# WikiHub-Mini.net
KiCad netlist of a schematic drawn in Altium Designer
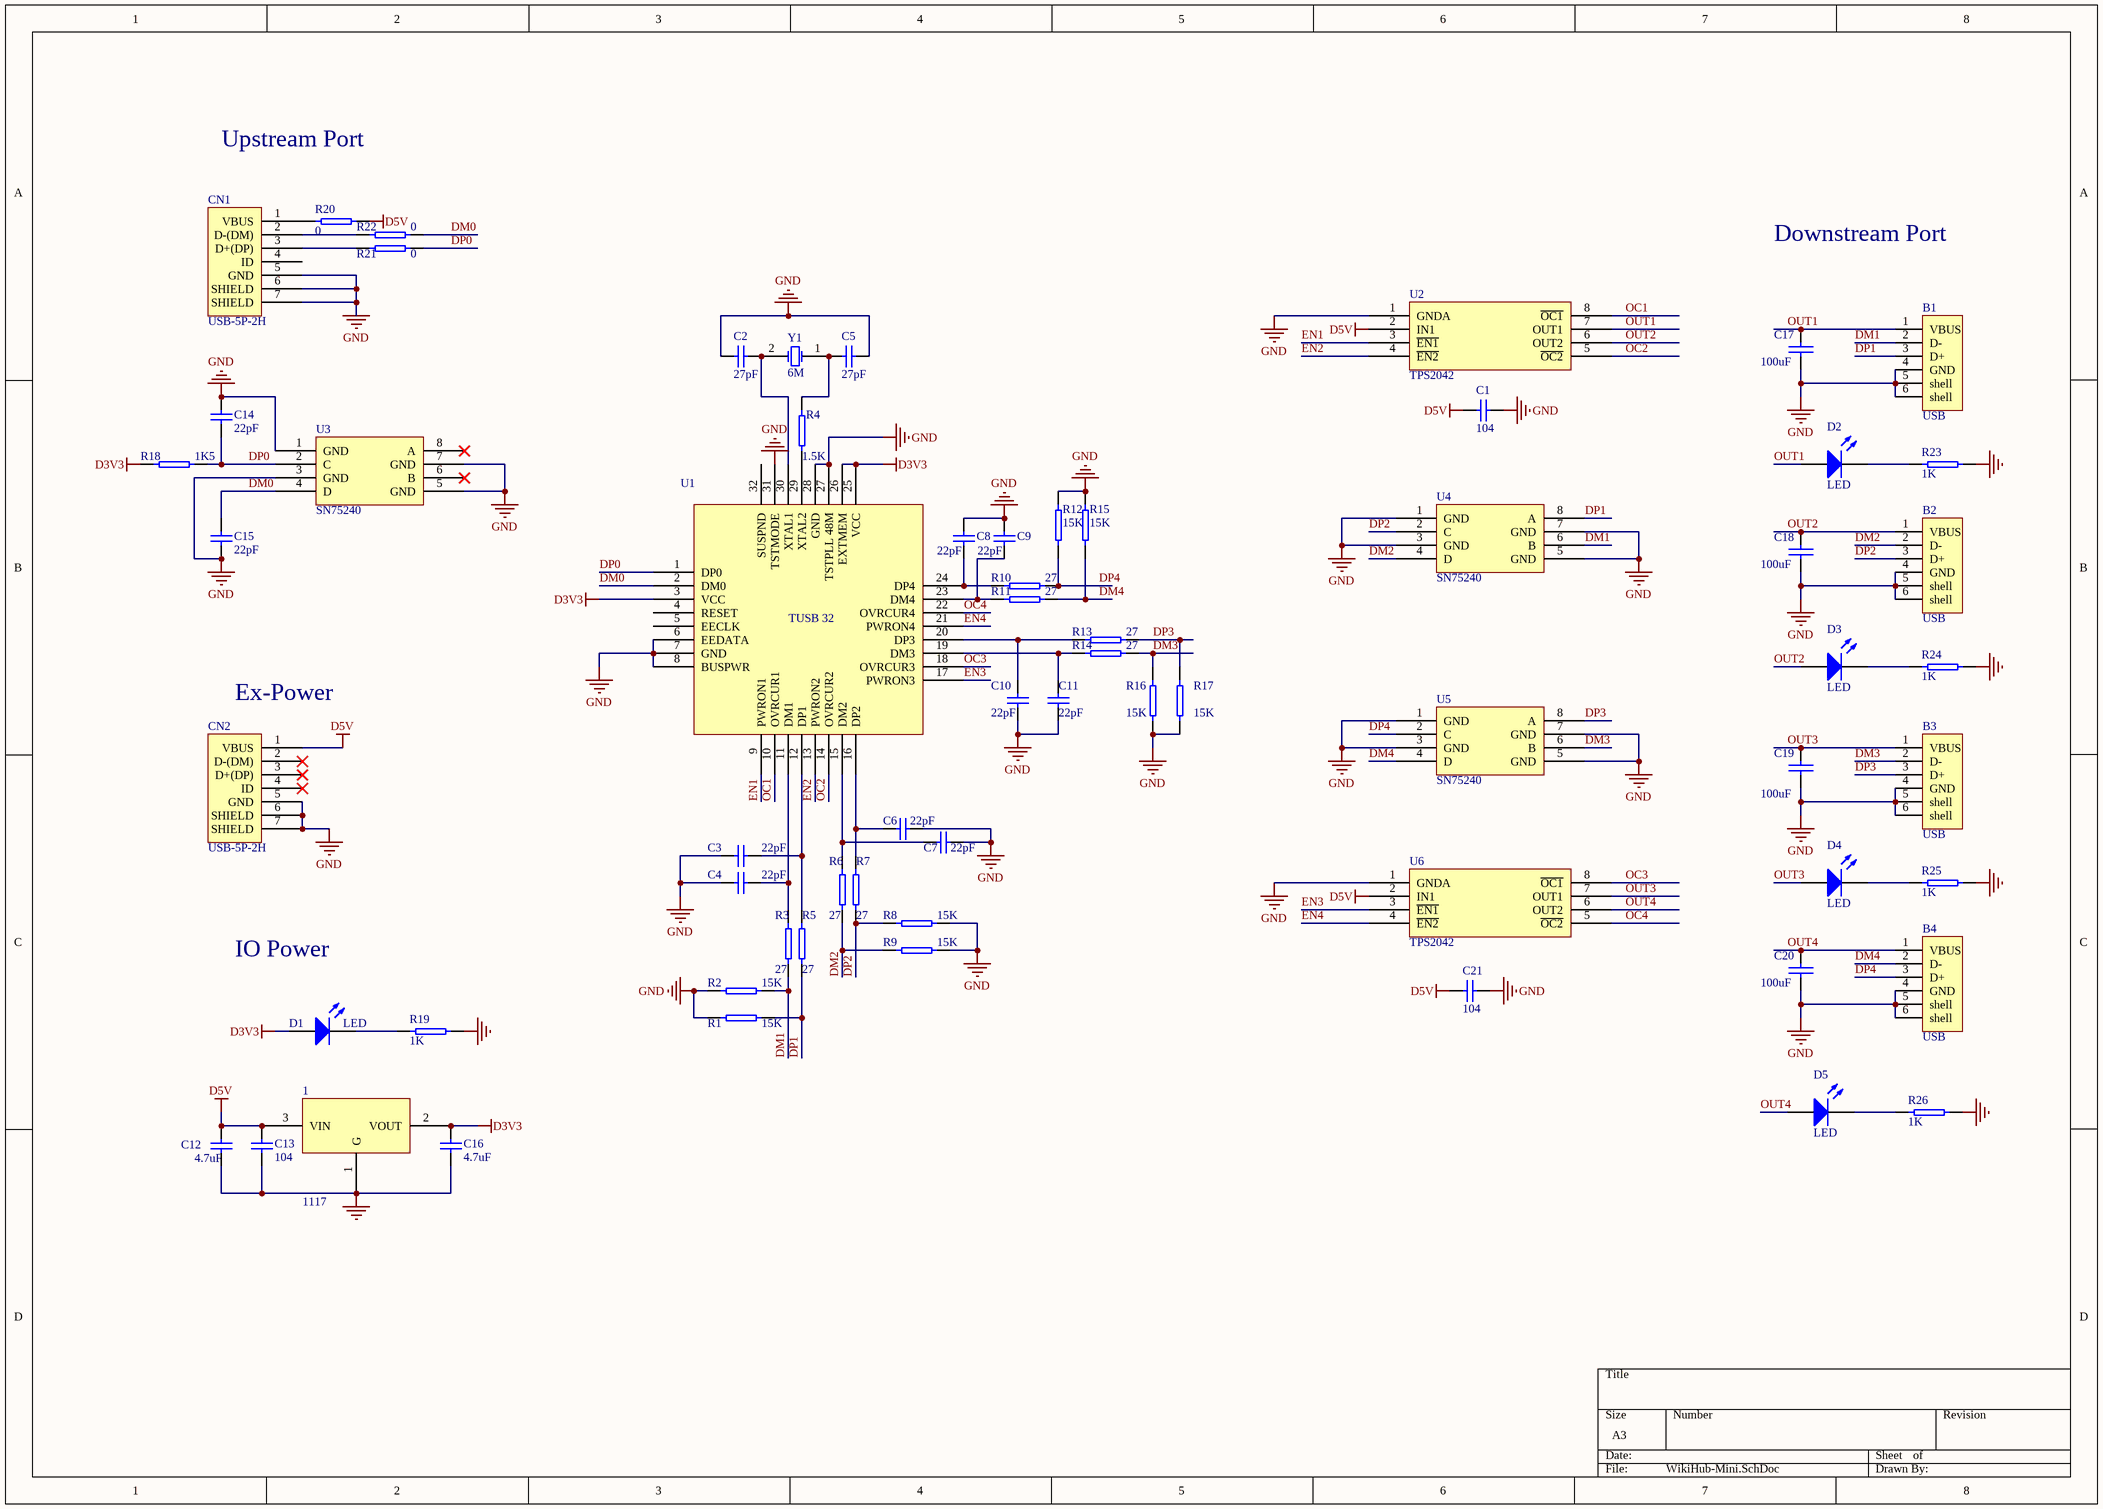
[diagram p0: WikiHub-Mini.SchDoc]

(export (version "E")
  (design (tool "Eeschema 10.0.6"))
  (components
    (comp (ref "1") (value "1117") (footprint "1117") (libsource (lib "原理图封装库") (part "117")))
    (comp (ref "B1") (value "USB") (footprint "USB-A-Female-T2-Lite") (libsource (lib "*") (part "USB")))
    (comp (ref "B2") (value "USB") (footprint "USB-A-Female-T2-Lite") (libsource (lib "*") (part "USB")))
    (comp (ref "B3") (value "USB") (footprint "USB-A-Female-T2-Lite") (libsource (lib "*") (part "USB")))
    (comp (ref "B4") (value "USB") (footprint "USB-A-Female-T2-Lite") (libsource (lib "*") (part "USB")))
    (comp (ref "C1")
      (value "104")
      (footprint "C0603L")
      (description "Capacitor")
      (fields (field (name "Comment") "Cap") (field (name "PUBLISHER") "Altium Limited"))
      (libsource (lib "Miscellaneous Devices") (part "Cap"))
    )
    (comp (ref "C2")
      (value "27pF")
      (footprint "C0603L")
      (description "Capacitor")
      (fields (field (name "PUBLISHER") "Altium Limited"))
      (libsource (lib "Miscellaneous Devices") (part "Cap"))
    )
    (comp (ref "C3")
      (value "22pF")
      (footprint "C0603L")
      (description "Capacitor")
      (fields (field (name "PUBLISHER") "Altium Limited"))
      (libsource (lib "Miscellaneous Devices") (part "Cap"))
    )
    (comp (ref "C4")
      (value "22pF")
      (footprint "C0603L")
      (description "Capacitor")
      (fields (field (name "PUBLISHER") "Altium Limited"))
      (libsource (lib "Miscellaneous Devices") (part "Cap"))
    )
    (comp (ref "C5")
      (value "27pF")
      (footprint "C0603L")
      (description "Capacitor")
      (fields (field (name "PUBLISHER") "Altium Limited"))
      (libsource (lib "Miscellaneous Devices") (part "Cap"))
    )
    (comp (ref "C6")
      (value "22pF")
      (footprint "C0603L")
      (description "Capacitor")
      (fields (field (name "PUBLISHER") "Altium Limited"))
      (libsource (lib "Miscellaneous Devices") (part "Cap"))
    )
    (comp (ref "C7")
      (value "22pF")
      (footprint "C0603L")
      (description "Capacitor")
      (fields (field (name "PUBLISHER") "Altium Limited"))
      (libsource (lib "Miscellaneous Devices") (part "Cap"))
    )
    (comp (ref "C8")
      (value "22pF")
      (footprint "C0603L")
      (description "Capacitor")
      (fields (field (name "PUBLISHER") "Altium Limited"))
      (libsource (lib "Miscellaneous Devices") (part "Cap"))
    )
    (comp (ref "C9")
      (value "22pF")
      (footprint "C0603L")
      (description "Capacitor")
      (fields (field (name "PUBLISHER") "Altium Limited"))
      (libsource (lib "Miscellaneous Devices") (part "Cap"))
    )
    (comp (ref "C10")
      (value "22pF")
      (footprint "C0603L")
      (description "Capacitor")
      (fields (field (name "PUBLISHER") "Altium Limited"))
      (libsource (lib "Miscellaneous Devices") (part "Cap"))
    )
    (comp (ref "C11")
      (value "22pF")
      (footprint "C0603L")
      (description "Capacitor")
      (fields (field (name "PUBLISHER") "Altium Limited"))
      (libsource (lib "Miscellaneous Devices") (part "Cap"))
    )
    (comp (ref "C12")
      (value "4.7uF")
      (footprint "C0603L")
      (description "Capacitor")
      (fields (field (name "Comment") "Cap") (field (name "PUBLISHER") "Altium Limited"))
      (libsource (lib "Miscellaneous Devices") (part "Cap"))
    )
    (comp (ref "C13")
      (value "104")
      (footprint "C0603L")
      (description "Capacitor")
      (fields (field (name "Comment") "Cap") (field (name "PUBLISHER") "Altium Limited"))
      (libsource (lib "Miscellaneous Devices") (part "Cap"))
    )
    (comp (ref "C14")
      (value "22pF")
      (footprint "C0603L")
      (description "Capacitor")
      (fields (field (name "PUBLISHER") "Altium Limited"))
      (libsource (lib "Miscellaneous Devices") (part "Cap"))
    )
    (comp (ref "C15")
      (value "22pF")
      (footprint "C0603L")
      (description "Capacitor")
      (fields (field (name "PUBLISHER") "Altium Limited"))
      (libsource (lib "Miscellaneous Devices") (part "Cap"))
    )
    (comp (ref "C16")
      (value "4.7uF")
      (footprint "C0603L")
      (description "Capacitor")
      (fields (field (name "Comment") "Cap") (field (name "PUBLISHER") "Altium Limited"))
      (libsource (lib "Miscellaneous Devices") (part "Cap"))
    )
    (comp (ref "C17")
      (value "100uF")
      (footprint "1210")
      (description "Capacitor")
      (libsource (lib "*") (part "CAP"))
    )
    (comp (ref "C18")
      (value "100uF")
      (footprint "1210")
      (description "Capacitor")
      (libsource (lib "*") (part "CAP"))
    )
    (comp (ref "C19")
      (value "100uF")
      (footprint "1210")
      (description "Capacitor")
      (libsource (lib "*") (part "CAP"))
    )
    (comp (ref "C20")
      (value "100uF")
      (footprint "1210")
      (description "Capacitor")
      (libsource (lib "*") (part "CAP"))
    )
    (comp (ref "C21")
      (value "104")
      (footprint "C0603L")
      (description "Capacitor")
      (fields (field (name "Comment") "Cap") (field (name "PUBLISHER") "Altium Limited"))
      (libsource (lib "Miscellaneous Devices") (part "Cap"))
    )
    (comp (ref "CN1")
      (value "USB-5P-2H")
      (footprint "USB-B-MICRO-Female-T3")
      (description "USB-M5P-2H")
      (libsource (lib "USB") (part "USB-5P-2H"))
    )
    (comp (ref "CN2")
      (value "USB-5P-2H")
      (footprint "USB-B-MICRO-Female-T3")
      (description "USB-M5P-2H")
      (libsource (lib "USB") (part "USB-5P-2H"))
    )
    (comp (ref "D1")
      (value "LED")
      (footprint "0603pn")
      (description "Typical INFRARED GaAs LED")
      (fields (field (name "PUBLISHER") "Altium Limited"))
      (libsource (lib "Miscellaneous Devices") (part "LED0"))
    )
    (comp (ref "D2")
      (value "LED")
      (footprint "0603pn")
      (description "Typical INFRARED GaAs LED")
      (fields (field (name "PUBLISHER") "Altium Limited"))
      (libsource (lib "Miscellaneous Devices") (part "LED0"))
    )
    (comp (ref "D3")
      (value "LED")
      (footprint "0603pn")
      (description "Typical INFRARED GaAs LED")
      (fields (field (name "PUBLISHER") "Altium Limited"))
      (libsource (lib "Miscellaneous Devices") (part "LED0"))
    )
    (comp (ref "D4")
      (value "LED")
      (footprint "0603pn")
      (description "Typical INFRARED GaAs LED")
      (fields (field (name "PUBLISHER") "Altium Limited"))
      (libsource (lib "Miscellaneous Devices") (part "LED0"))
    )
    (comp (ref "D5")
      (value "LED")
      (footprint "0603pn")
      (description "Typical INFRARED GaAs LED")
      (fields (field (name "PUBLISHER") "Altium Limited"))
      (libsource (lib "Miscellaneous Devices") (part "LED0"))
    )
    (comp (ref "R1") (value "15K") (footprint "R0603") (libsource (lib "原理图封装库") (part "RES")))
    (comp (ref "R2") (value "15K") (footprint "R0603") (libsource (lib "原理图封装库") (part "RES")))
    (comp (ref "R3") (value "27") (footprint "R0603") (libsource (lib "原理图封装库") (part "RES")))
    (comp (ref "R4") (value "1.5K") (footprint "R0603") (libsource (lib "原理图封装库") (part "RES")))
    (comp (ref "R5") (value "27") (footprint "R0603") (libsource (lib "原理图封装库") (part "RES")))
    (comp (ref "R6") (value "27") (footprint "R0603") (libsource (lib "原理图封装库") (part "RES")))
    (comp (ref "R7") (value "27") (footprint "R0603") (libsource (lib "原理图封装库") (part "RES")))
    (comp (ref "R8") (value "15K") (footprint "R0603") (libsource (lib "原理图封装库") (part "RES")))
    (comp (ref "R9") (value "15K") (footprint "R0603") (libsource (lib "原理图封装库") (part "RES")))
    (comp (ref "R10") (value "27") (footprint "R0603") (libsource (lib "原理图封装库") (part "RES")))
    (comp (ref "R11") (value "27") (footprint "R0603") (libsource (lib "原理图封装库") (part "RES")))
    (comp (ref "R12") (value "15K") (footprint "R0603") (libsource (lib "原理图封装库") (part "RES")))
    (comp (ref "R13") (value "27") (footprint "R0603") (libsource (lib "原理图封装库") (part "RES")))
    (comp (ref "R14") (value "27") (footprint "R0603") (libsource (lib "原理图封装库") (part "RES")))
    (comp (ref "R15") (value "15K") (footprint "R0603") (libsource (lib "原理图封装库") (part "RES")))
    (comp (ref "R16") (value "15K") (footprint "R0603") (libsource (lib "原理图封装库") (part "RES")))
    (comp (ref "R17") (value "15K") (footprint "R0603") (libsource (lib "原理图封装库") (part "RES")))
    (comp (ref "R18") (value "1K5") (footprint "R0603") (libsource (lib "原理图封装库") (part "RES")))
    (comp (ref "R19") (value "1K") (footprint "R0603") (libsource (lib "原理图封装库") (part "RES")))
    (comp (ref "R20") (value "0") (footprint "R0603") (libsource (lib "原理图封装库") (part "RES")))
    (comp (ref "R21") (value "0") (footprint "R0603") (libsource (lib "原理图封装库") (part "RES")))
    (comp (ref "R22") (value "0") (footprint "R0603") (libsource (lib "原理图封装库") (part "RES")))
    (comp (ref "R23") (value "1K") (footprint "R0603") (libsource (lib "原理图封装库") (part "RES")))
    (comp (ref "R24") (value "1K") (footprint "R0603") (libsource (lib "原理图封装库") (part "RES")))
    (comp (ref "R25") (value "1K") (footprint "R0603") (libsource (lib "原理图封装库") (part "RES")))
    (comp (ref "R26") (value "1K") (footprint "R0603") (libsource (lib "原理图封装库") (part "RES")))
    (comp (ref "U1") (value "TUSB 32") (footprint "TQFP32") (libsource (lib "rhyme-SCH") (part "TUSB 32")))
    (comp (ref "U2") (value "TPS2042") (footprint "SO8W_M") (libsource (lib "WikiHub") (part "TPS2042")))
    (comp (ref "U3")
      (value "SN75240")
      (footprint "SOP8 - 0.65")
      (libsource (lib "rhyme-SCH") (part "SN75240"))
    )
    (comp (ref "U4")
      (value "SN75240")
      (footprint "SOP8 - 0.65")
      (libsource (lib "rhyme-SCH") (part "SN75240"))
    )
    (comp (ref "U5")
      (value "SN75240")
      (footprint "SOP8 - 0.65")
      (libsource (lib "rhyme-SCH") (part "SN75240"))
    )
    (comp (ref "U6") (value "TPS2042") (footprint "SO8W_M") (libsource (lib "WikiHub") (part "TPS2042")))
    (comp (ref "Y1")
      (value "6M")
      (footprint "XTAL")
      (description "Crystal Oscillator")
      (fields (field (name "PUBLISHER") "Altium Limited"))
      (libsource (lib "Miscellaneous Devices") (part "XTAL"))
    )
  )
  (nets
    (net (code "1") (name "/DM0") (class "Default")
      (node (ref "C15") (pin "1") (pinfunction "1_1") (pintype "passive"))
      (node (ref "R22") (pin "1") (pinfunction "1_1") (pintype "passive"))
      (node (ref "U1") (pin "2") (pinfunction "DM0_2") (pintype "passive"))
      (node (ref "U3") (pin "4") (pinfunction "D_4") (pintype "passive"))
    )
    (net (code "2") (name "/DM1") (class "Default")
      (node (ref "B1") (pin "2") (pinfunction "D-_2") (pintype "passive"))
      (node (ref "R2") (pin "1") (pinfunction "1_1") (pintype "passive"))
      (node (ref "R3") (pin "1") (pinfunction "1_1") (pintype "passive"))
      (node (ref "U4") (pin "6") (pinfunction "B_6") (pintype "passive"))
    )
    (net (code "3") (name "/DM2") (class "Default")
      (node (ref "B2") (pin "2") (pinfunction "D-_2") (pintype "passive"))
      (node (ref "R6") (pin "1") (pinfunction "1_1") (pintype "passive"))
      (node (ref "R9") (pin "2") (pinfunction "2_2") (pintype "passive"))
      (node (ref "U4") (pin "4") (pinfunction "D_4") (pintype "passive"))
    )
    (net (code "4") (name "/DM3") (class "Default")
      (node (ref "B3") (pin "2") (pinfunction "D-_2") (pintype "passive"))
      (node (ref "R14") (pin "1") (pinfunction "1_1") (pintype "passive"))
      (node (ref "R16") (pin "1") (pinfunction "1_1") (pintype "passive"))
      (node (ref "U5") (pin "6") (pinfunction "B_6") (pintype "passive"))
    )
    (net (code "5") (name "/DM4") (class "Default")
      (node (ref "B4") (pin "2") (pinfunction "D-_2") (pintype "passive"))
      (node (ref "R11") (pin "1") (pinfunction "1_1") (pintype "passive"))
      (node (ref "R15") (pin "2") (pinfunction "2_2") (pintype "passive"))
      (node (ref "U5") (pin "4") (pinfunction "D_4") (pintype "passive"))
    )
    (net (code "6") (name "/DP0") (class "Default")
      (node (ref "C14") (pin "2") (pinfunction "2_2") (pintype "passive"))
      (node (ref "R18") (pin "1") (pinfunction "1_1") (pintype "passive"))
      (node (ref "R21") (pin "1") (pinfunction "1_1") (pintype "passive"))
      (node (ref "U1") (pin "1") (pinfunction "DP0_1") (pintype "passive"))
      (node (ref "U3") (pin "2") (pinfunction "C_2") (pintype "passive"))
    )
    (net (code "7") (name "/DP1") (class "Default")
      (node (ref "B1") (pin "3") (pinfunction "D+_3") (pintype "passive"))
      (node (ref "R1") (pin "1") (pinfunction "1_1") (pintype "passive"))
      (node (ref "R5") (pin "1") (pinfunction "1_1") (pintype "passive"))
      (node (ref "U4") (pin "8") (pinfunction "A_8") (pintype "passive"))
    )
    (net (code "8") (name "/DP2") (class "Default")
      (node (ref "B2") (pin "3") (pinfunction "D+_3") (pintype "passive"))
      (node (ref "R7") (pin "1") (pinfunction "1_1") (pintype "passive"))
      (node (ref "R8") (pin "2") (pinfunction "2_2") (pintype "passive"))
      (node (ref "U4") (pin "2") (pinfunction "C_2") (pintype "passive"))
    )
    (net (code "9") (name "/DP3") (class "Default")
      (node (ref "B3") (pin "3") (pinfunction "D+_3") (pintype "passive"))
      (node (ref "R13") (pin "1") (pinfunction "1_1") (pintype "passive"))
      (node (ref "R17") (pin "1") (pinfunction "1_1") (pintype "passive"))
      (node (ref "U5") (pin "8") (pinfunction "A_8") (pintype "passive"))
    )
    (net (code "10") (name "/DP4") (class "Default")
      (node (ref "B4") (pin "3") (pinfunction "D+_3") (pintype "passive"))
      (node (ref "R10") (pin "1") (pinfunction "1_1") (pintype "passive"))
      (node (ref "R12") (pin "2") (pinfunction "2_2") (pintype "passive"))
      (node (ref "U5") (pin "2") (pinfunction "C_2") (pintype "passive"))
    )
    (net (code "11") (name "/EN1") (class "Default")
      (node (ref "U1") (pin "9") (pinfunction "PWRON1_9") (pintype "passive"))
      (node (ref "U2") (pin "3") (pinfunction "~{EN1}_3") (pintype "passive"))
    )
    (net (code "12") (name "/EN2") (class "Default")
      (node (ref "U1") (pin "13") (pinfunction "PWRON2_13") (pintype "passive"))
      (node (ref "U2") (pin "4") (pinfunction "~{EN2}_4") (pintype "passive"))
    )
    (net (code "13") (name "/EN3") (class "Default")
      (node (ref "U1") (pin "17") (pinfunction "PWRON3_17") (pintype "passive"))
      (node (ref "U6") (pin "3") (pinfunction "~{EN1}_3") (pintype "passive"))
    )
    (net (code "14") (name "/EN4") (class "Default")
      (node (ref "U1") (pin "21") (pinfunction "PWRON4_21") (pintype "passive"))
      (node (ref "U6") (pin "4") (pinfunction "~{EN2}_4") (pintype "passive"))
    )
    (net (code "15") (name "/OC1") (class "Default")
      (node (ref "U1") (pin "10") (pinfunction "OVRCUR1_10") (pintype "passive"))
      (node (ref "U2") (pin "8") (pinfunction "~{OC1}_8") (pintype "passive"))
    )
    (net (code "16") (name "/OC2") (class "Default")
      (node (ref "U1") (pin "14") (pinfunction "OVRCUR2_14") (pintype "passive"))
      (node (ref "U2") (pin "5") (pinfunction "~{OC2}_5") (pintype "passive"))
    )
    (net (code "17") (name "/OC3") (class "Default")
      (node (ref "U1") (pin "18") (pinfunction "OVRCUR3_18") (pintype "passive"))
      (node (ref "U6") (pin "8") (pinfunction "~{OC1}_8") (pintype "passive"))
    )
    (net (code "18") (name "/OC4") (class "Default")
      (node (ref "U1") (pin "22") (pinfunction "OVRCUR4_22") (pintype "passive"))
      (node (ref "U6") (pin "5") (pinfunction "~{OC2}_5") (pintype "passive"))
    )
    (net (code "19") (name "/OUT1") (class "Default")
      (node (ref "B1") (pin "1") (pinfunction "VBUS_1") (pintype "passive"))
      (node (ref "C17") (pin "1") (pinfunction "1_1") (pintype "passive"))
      (node (ref "D2") (pin "1") (pinfunction "A_1") (pintype "passive"))
      (node (ref "U2") (pin "7") (pinfunction "OUT1_7") (pintype "passive"))
    )
    (net (code "20") (name "/OUT2") (class "Default")
      (node (ref "B2") (pin "1") (pinfunction "VBUS_1") (pintype "passive"))
      (node (ref "C18") (pin "1") (pinfunction "1_1") (pintype "passive"))
      (node (ref "D3") (pin "1") (pinfunction "A_1") (pintype "passive"))
      (node (ref "U2") (pin "6") (pinfunction "OUT2_6") (pintype "passive"))
    )
    (net (code "21") (name "/OUT3") (class "Default")
      (node (ref "B3") (pin "1") (pinfunction "VBUS_1") (pintype "passive"))
      (node (ref "C19") (pin "1") (pinfunction "1_1") (pintype "passive"))
      (node (ref "D4") (pin "1") (pinfunction "A_1") (pintype "passive"))
      (node (ref "U6") (pin "7") (pinfunction "OUT1_7") (pintype "passive"))
    )
    (net (code "22") (name "/OUT4") (class "Default")
      (node (ref "B4") (pin "1") (pinfunction "VBUS_1") (pintype "passive"))
      (node (ref "C20") (pin "1") (pinfunction "1_1") (pintype "passive"))
      (node (ref "D5") (pin "1") (pinfunction "A_1") (pintype "passive"))
      (node (ref "U6") (pin "6") (pinfunction "OUT2_6") (pintype "passive"))
    )
    (net (code "23") (name "D3V3") (class "Default")
      (node (ref "1") (pin "2") (pinfunction "VOUT_2") (pintype "passive"))
      (node (ref "C16") (pin "2") (pinfunction "2_2") (pintype "passive"))
      (node (ref "D1") (pin "1") (pinfunction "A_1") (pintype "passive"))
      (node (ref "R18") (pin "2") (pinfunction "2_2") (pintype "passive"))
      (node (ref "U1") (pin "25") (pinfunction "VCC_25") (pintype "passive"))
      (node (ref "U1") (pin "26") (pinfunction "EXTMEM_26") (pintype "passive"))
      (node (ref "U1") (pin "3") (pinfunction "VCC_3") (pintype "passive"))
    )
    (net (code "24") (name "D5V") (class "Default")
      (node (ref "1") (pin "3") (pinfunction "VIN_3") (pintype "passive"))
      (node (ref "C1") (pin "2") (pinfunction "2_2") (pintype "passive"))
      (node (ref "C12") (pin "2") (pinfunction "2_2") (pintype "passive"))
      (node (ref "C13") (pin "2") (pinfunction "2_2") (pintype "passive"))
      (node (ref "C21") (pin "2") (pinfunction "2_2") (pintype "passive"))
      (node (ref "CN2") (pin "1") (pinfunction "VBUS_1") (pintype "passive"))
      (node (ref "R20") (pin "1") (pinfunction "1_1") (pintype "passive"))
      (node (ref "U2") (pin "2") (pinfunction "IN1_2") (pintype "passive"))
      (node (ref "U6") (pin "2") (pinfunction "IN1_2") (pintype "passive"))
    )
    (net (code "25") (name "GND") (class "Default")
      (node (ref "1") (pin "1") (pinfunction "G_1") (pintype "passive"))
      (node (ref "B1") (pin "4") (pinfunction "GND_4") (pintype "passive"))
      (node (ref "B1") (pin "5") (pinfunction "shell_5") (pintype "passive"))
      (node (ref "B1") (pin "6") (pinfunction "shell_6") (pintype "passive"))
      (node (ref "B2") (pin "4") (pinfunction "GND_4") (pintype "passive"))
      (node (ref "B2") (pin "5") (pinfunction "shell_5") (pintype "passive"))
      (node (ref "B2") (pin "6") (pinfunction "shell_6") (pintype "passive"))
      (node (ref "B3") (pin "4") (pinfunction "GND_4") (pintype "passive"))
      (node (ref "B3") (pin "5") (pinfunction "shell_5") (pintype "passive"))
      (node (ref "B3") (pin "6") (pinfunction "shell_6") (pintype "passive"))
      (node (ref "B4") (pin "4") (pinfunction "GND_4") (pintype "passive"))
      (node (ref "B4") (pin "5") (pinfunction "shell_5") (pintype "passive"))
      (node (ref "B4") (pin "6") (pinfunction "shell_6") (pintype "passive"))
      (node (ref "C1") (pin "1") (pinfunction "1_1") (pintype "passive"))
      (node (ref "C10") (pin "1") (pinfunction "1_1") (pintype "passive"))
      (node (ref "C11") (pin "1") (pinfunction "1_1") (pintype "passive"))
      (node (ref "C12") (pin "1") (pinfunction "1_1") (pintype "passive"))
      (node (ref "C13") (pin "1") (pinfunction "1_1") (pintype "passive"))
      (node (ref "C14") (pin "1") (pinfunction "1_1") (pintype "passive"))
      (node (ref "C15") (pin "2") (pinfunction "2_2") (pintype "passive"))
      (node (ref "C16") (pin "1") (pinfunction "1_1") (pintype "passive"))
      (node (ref "C17") (pin "2") (pinfunction "2_2") (pintype "passive"))
      (node (ref "C18") (pin "2") (pinfunction "2_2") (pintype "passive"))
      (node (ref "C19") (pin "2") (pinfunction "2_2") (pintype "passive"))
      (node (ref "C2") (pin "2") (pinfunction "2_2") (pintype "passive"))
      (node (ref "C20") (pin "2") (pinfunction "2_2") (pintype "passive"))
      (node (ref "C21") (pin "1") (pinfunction "1_1") (pintype "passive"))
      (node (ref "C3") (pin "1") (pinfunction "1_1") (pintype "passive"))
      (node (ref "C4") (pin "1") (pinfunction "1_1") (pintype "passive"))
      (node (ref "C5") (pin "2") (pinfunction "2_2") (pintype "passive"))
      (node (ref "C6") (pin "2") (pinfunction "2_2") (pintype "passive"))
      (node (ref "C7") (pin "2") (pinfunction "2_2") (pintype "passive"))
      (node (ref "C8") (pin "2") (pinfunction "2_2") (pintype "passive"))
      (node (ref "C9") (pin "2") (pinfunction "2_2") (pintype "passive"))
      (node (ref "CN1") (pin "5") (pinfunction "GND_5") (pintype "passive"))
      (node (ref "CN1") (pin "6") (pinfunction "SHIELD_6") (pintype "passive"))
      (node (ref "CN1") (pin "7") (pinfunction "SHIELD_7") (pintype "passive"))
      (node (ref "CN2") (pin "5") (pinfunction "GND_5") (pintype "passive"))
      (node (ref "CN2") (pin "6") (pinfunction "SHIELD_6") (pintype "passive"))
      (node (ref "CN2") (pin "7") (pinfunction "SHIELD_7") (pintype "passive"))
      (node (ref "R1") (pin "2") (pinfunction "2_2") (pintype "passive"))
      (node (ref "R12") (pin "1") (pinfunction "1_1") (pintype "passive"))
      (node (ref "R15") (pin "1") (pinfunction "1_1") (pintype "passive"))
      (node (ref "R16") (pin "2") (pinfunction "2_2") (pintype "passive"))
      (node (ref "R17") (pin "2") (pinfunction "2_2") (pintype "passive"))
      (node (ref "R19") (pin "1") (pinfunction "1_1") (pintype "passive"))
      (node (ref "R2") (pin "2") (pinfunction "2_2") (pintype "passive"))
      (node (ref "R23") (pin "1") (pinfunction "1_1") (pintype "passive"))
      (node (ref "R24") (pin "1") (pinfunction "1_1") (pintype "passive"))
      (node (ref "R25") (pin "1") (pinfunction "1_1") (pintype "passive"))
      (node (ref "R26") (pin "1") (pinfunction "1_1") (pintype "passive"))
      (node (ref "R8") (pin "1") (pinfunction "1_1") (pintype "passive"))
      (node (ref "R9") (pin "1") (pinfunction "1_1") (pintype "passive"))
      (node (ref "U1") (pin "27") (pinfunction "TSTPLL_48M_27") (pintype "passive"))
      (node (ref "U1") (pin "28") (pinfunction "GND_28") (pintype "passive"))
      (node (ref "U1") (pin "31") (pinfunction "TSTMODE_31") (pintype "passive"))
      (node (ref "U1") (pin "6") (pinfunction "EEDATA_6") (pintype "passive"))
      (node (ref "U1") (pin "7") (pinfunction "GND_7") (pintype "passive"))
      (node (ref "U1") (pin "8") (pinfunction "BUSPWR_8") (pintype "passive"))
      (node (ref "U2") (pin "1") (pinfunction "GNDA_1") (pintype "passive"))
      (node (ref "U3") (pin "1") (pinfunction "GND_1") (pintype "passive"))
      (node (ref "U3") (pin "3") (pinfunction "GND_3") (pintype "passive"))
      (node (ref "U3") (pin "5") (pinfunction "GND_5") (pintype "passive"))
      (node (ref "U3") (pin "7") (pinfunction "GND_7") (pintype "passive"))
      (node (ref "U4") (pin "1") (pinfunction "GND_1") (pintype "passive"))
      (node (ref "U4") (pin "3") (pinfunction "GND_3") (pintype "passive"))
      (node (ref "U4") (pin "5") (pinfunction "GND_5") (pintype "passive"))
      (node (ref "U4") (pin "7") (pinfunction "GND_7") (pintype "passive"))
      (node (ref "U5") (pin "1") (pinfunction "GND_1") (pintype "passive"))
      (node (ref "U5") (pin "3") (pinfunction "GND_3") (pintype "passive"))
      (node (ref "U5") (pin "5") (pinfunction "GND_5") (pintype "passive"))
      (node (ref "U5") (pin "7") (pinfunction "GND_7") (pintype "passive"))
      (node (ref "U6") (pin "1") (pinfunction "GNDA_1") (pintype "passive"))
    )
    (net (code "26") (name "Net-(CN1-D+(DP))") (class "Default")
      (node (ref "CN1") (pin "3") (pinfunction "D+(DP)_3") (pintype "passive"))
      (node (ref "R21") (pin "2") (pinfunction "2_2") (pintype "passive"))
    )
    (net (code "27") (name "Net-(CN1-D-(DM))") (class "Default")
      (node (ref "CN1") (pin "2") (pinfunction "D-(DM)_2") (pintype "passive"))
      (node (ref "R22") (pin "2") (pinfunction "2_2") (pintype "passive"))
    )
    (net (code "28") (name "Net-(CN1-VBUS)") (class "Default")
      (node (ref "CN1") (pin "1") (pinfunction "VBUS_1") (pintype "passive"))
      (node (ref "R20") (pin "2") (pinfunction "2_2") (pintype "passive"))
    )
    (net (code "29") (name "Net-(D1-K)") (class "Default")
      (node (ref "D1") (pin "2") (pinfunction "K_2") (pintype "passive"))
      (node (ref "R19") (pin "2") (pinfunction "2_2") (pintype "passive"))
    )
    (net (code "30") (name "Net-(D2-K)") (class "Default")
      (node (ref "D2") (pin "2") (pinfunction "K_2") (pintype "passive"))
      (node (ref "R23") (pin "2") (pinfunction "2_2") (pintype "passive"))
    )
    (net (code "31") (name "Net-(D3-K)") (class "Default")
      (node (ref "D3") (pin "2") (pinfunction "K_2") (pintype "passive"))
      (node (ref "R24") (pin "2") (pinfunction "2_2") (pintype "passive"))
    )
    (net (code "32") (name "Net-(D4-K)") (class "Default")
      (node (ref "D4") (pin "2") (pinfunction "K_2") (pintype "passive"))
      (node (ref "R25") (pin "2") (pinfunction "2_2") (pintype "passive"))
    )
    (net (code "33") (name "Net-(D5-K)") (class "Default")
      (node (ref "D5") (pin "2") (pinfunction "K_2") (pintype "passive"))
      (node (ref "R26") (pin "2") (pinfunction "2_2") (pintype "passive"))
    )
    (net (code "34") (name "Net-(U1-DM1)") (class "Default")
      (node (ref "C4") (pin "2") (pinfunction "2_2") (pintype "passive"))
      (node (ref "R3") (pin "2") (pinfunction "2_2") (pintype "passive"))
      (node (ref "U1") (pin "11") (pinfunction "DM1_11") (pintype "passive"))
    )
    (net (code "35") (name "Net-(U1-DM2)") (class "Default")
      (node (ref "C7") (pin "1") (pinfunction "1_1") (pintype "passive"))
      (node (ref "R6") (pin "2") (pinfunction "2_2") (pintype "passive"))
      (node (ref "U1") (pin "15") (pinfunction "DM2_15") (pintype "passive"))
    )
    (net (code "36") (name "Net-(U1-DM3)") (class "Default")
      (node (ref "C11") (pin "2") (pinfunction "2_2") (pintype "passive"))
      (node (ref "R14") (pin "2") (pinfunction "2_2") (pintype "passive"))
      (node (ref "U1") (pin "19") (pinfunction "DM3_19") (pintype "passive"))
    )
    (net (code "37") (name "Net-(U1-DM4)") (class "Default")
      (node (ref "C9") (pin "1") (pinfunction "1_1") (pintype "passive"))
      (node (ref "R11") (pin "2") (pinfunction "2_2") (pintype "passive"))
      (node (ref "U1") (pin "23") (pinfunction "DM4_23") (pintype "passive"))
    )
    (net (code "38") (name "Net-(U1-DP1)") (class "Default")
      (node (ref "C3") (pin "2") (pinfunction "2_2") (pintype "passive"))
      (node (ref "R5") (pin "2") (pinfunction "2_2") (pintype "passive"))
      (node (ref "U1") (pin "12") (pinfunction "DP1_12") (pintype "passive"))
    )
    (net (code "39") (name "Net-(U1-DP2)") (class "Default")
      (node (ref "C6") (pin "1") (pinfunction "1_1") (pintype "passive"))
      (node (ref "R7") (pin "2") (pinfunction "2_2") (pintype "passive"))
      (node (ref "U1") (pin "16") (pinfunction "DP2_16") (pintype "passive"))
    )
    (net (code "40") (name "Net-(U1-DP3)") (class "Default")
      (node (ref "C10") (pin "2") (pinfunction "2_2") (pintype "passive"))
      (node (ref "R13") (pin "2") (pinfunction "2_2") (pintype "passive"))
      (node (ref "U1") (pin "20") (pinfunction "DP3_20") (pintype "passive"))
    )
    (net (code "41") (name "Net-(U1-DP4)") (class "Default")
      (node (ref "C8") (pin "1") (pinfunction "1_1") (pintype "passive"))
      (node (ref "R10") (pin "2") (pinfunction "2_2") (pintype "passive"))
      (node (ref "U1") (pin "24") (pinfunction "DP4_24") (pintype "passive"))
    )
    (net (code "42") (name "Net-(U1-XTAL1)") (class "Default")
      (node (ref "C2") (pin "1") (pinfunction "1_1") (pintype "passive"))
      (node (ref "U1") (pin "30") (pinfunction "XTAL1_30") (pintype "passive"))
      (node (ref "Y1") (pin "2") (pinfunction "OSC2_2") (pintype "passive"))
    )
    (net (code "43") (name "Net-(U1-XTAL2)") (class "Default")
      (node (ref "R4") (pin "2") (pinfunction "2_2") (pintype "passive"))
      (node (ref "U1") (pin "29") (pinfunction "XTAL2_29") (pintype "passive"))
    )
    (net (code "44") (name "Net-(Y1-OSC1)") (class "Default")
      (node (ref "C5") (pin "1") (pinfunction "1_1") (pintype "passive"))
      (node (ref "R4") (pin "1") (pinfunction "1_1") (pintype "passive"))
      (node (ref "Y1") (pin "1") (pinfunction "OSC1_1") (pintype "passive"))
    )
    (net (code "45") (name "unconnected-(CN1-ID-Pad4)") (class "Default")
      (node (ref "CN1") (pin "4") (pinfunction "ID_4") (pintype "passive"))
    )
    (net (code "46") (name "unconnected-(CN2-D+(DP)-Pad3)") (class "Default")
      (node (ref "CN2") (pin "3") (pinfunction "D+(DP)_3") (pintype "passive+no_connect"))
    )
    (net (code "47") (name "unconnected-(CN2-D-(DM)-Pad2)") (class "Default")
      (node (ref "CN2") (pin "2") (pinfunction "D-(DM)_2") (pintype "passive+no_connect"))
    )
    (net (code "48") (name "unconnected-(CN2-ID-Pad4)") (class "Default")
      (node (ref "CN2") (pin "4") (pinfunction "ID_4") (pintype "passive+no_connect"))
    )
    (net (code "49") (name "unconnected-(U1-EECLK-Pad5)") (class "Default")
      (node (ref "U1") (pin "5") (pinfunction "EECLK_5") (pintype "passive"))
    )
    (net (code "50") (name "unconnected-(U1-RESET-Pad4)") (class "Default")
      (node (ref "U1") (pin "4") (pinfunction "RESET_4") (pintype "passive"))
    )
    (net (code "51") (name "unconnected-(U1-SUSPND-Pad32)") (class "Default")
      (node (ref "U1") (pin "32") (pinfunction "SUSPND_32") (pintype "passive"))
    )
    (net (code "52") (name "unconnected-(U3-A-Pad8)") (class "Default")
      (node (ref "U3") (pin "8") (pinfunction "A_8") (pintype "passive+no_connect"))
    )
    (net (code "53") (name "unconnected-(U3-B-Pad6)") (class "Default")
      (node (ref "U3") (pin "6") (pinfunction "B_6") (pintype "passive+no_connect"))
    )
  )
)
